# AltoidsCanary.net
KiCad netlist of a schematic drawn in EasyEDA
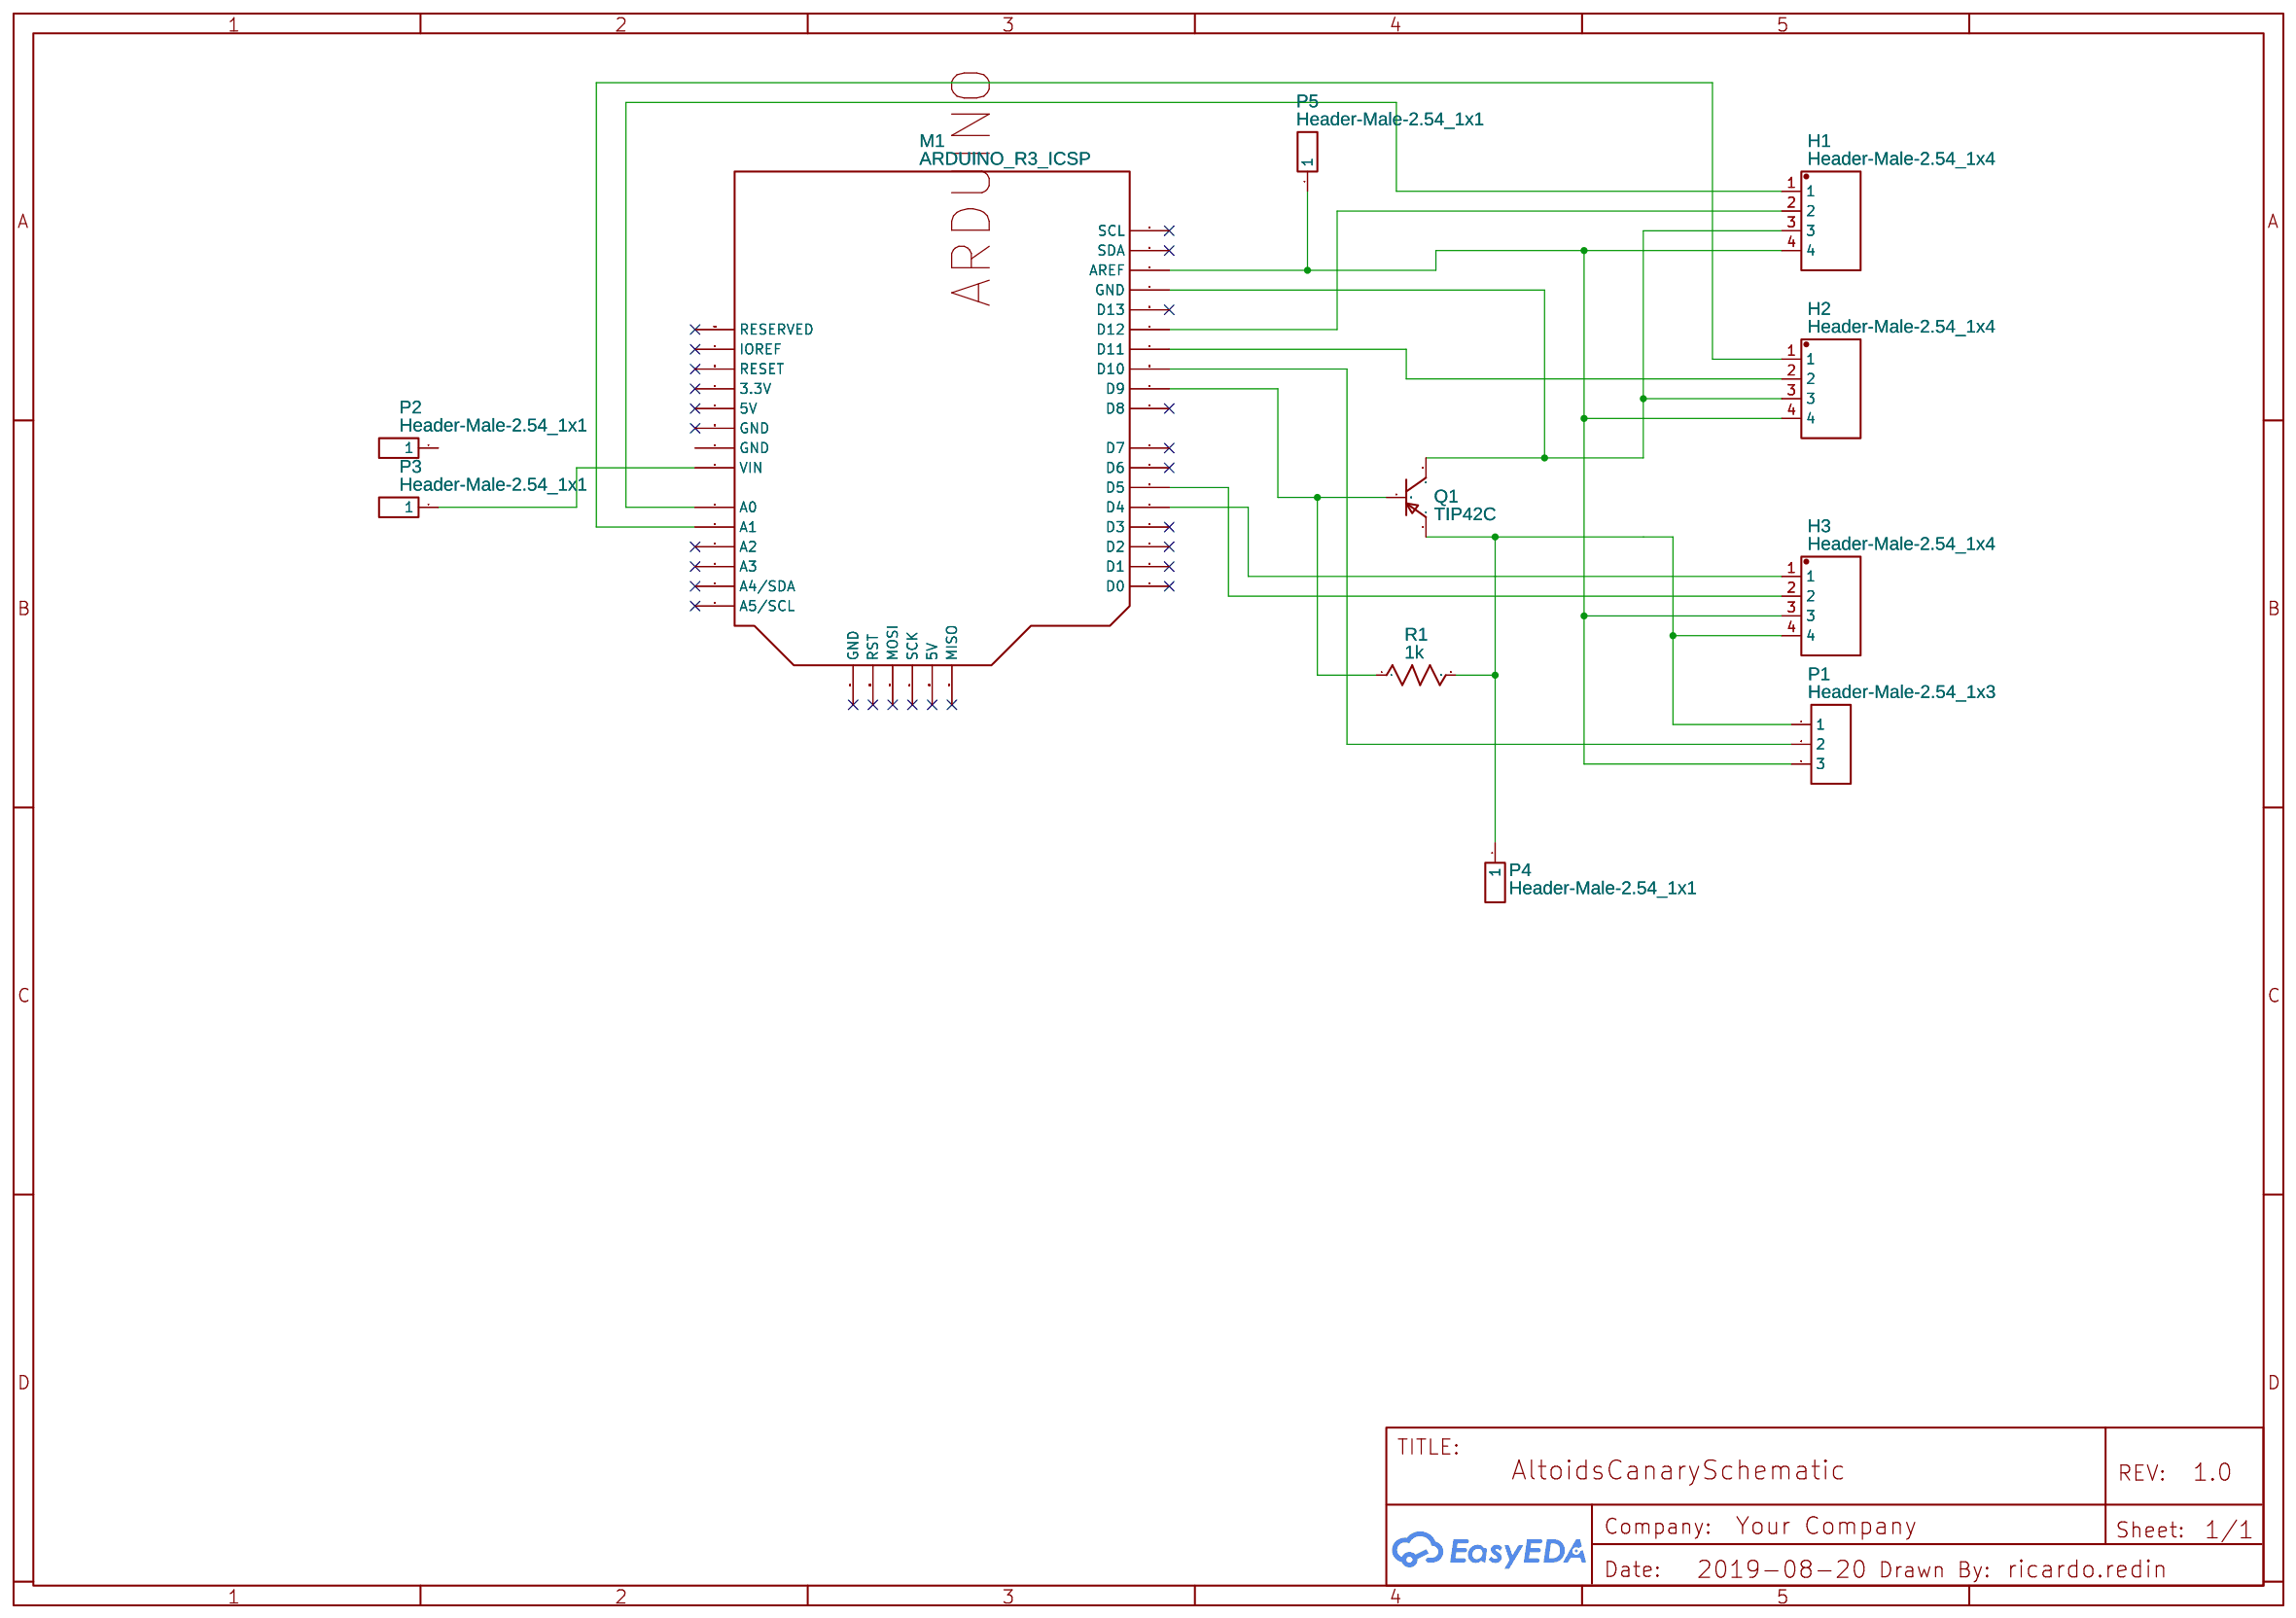
[diagram p0: schematic sheet]

(export (version "E")
  (design (tool "Eeschema 10.0.6"))
  (components
    (comp (ref "H1")
      (value "Header-Male-2.54_1x4")
      (fields
        (field (name "BOM_Manufacturer Part") "210S-1*4P L=11.6MMGold-plated black")
        (field (name "BOM_Supplier Part") "C124378")
      )
      (libsource (lib "") (part "Unknown_915_105"))
    )
    (comp (ref "H2")
      (value "Header-Male-2.54_1x4")
      (fields
        (field (name "BOM_Manufacturer Part") "210S-1*4P L=11.6MMGold-plated black")
        (field (name "BOM_Supplier Part") "C124378")
      )
      (libsource (lib "") (part "Unknown_915_190"))
    )
    (comp (ref "H3")
      (value "Header-Male-2.54_1x4")
      (fields
        (field (name "BOM_Manufacturer Part") "210S-1*4P L=11.6MMGold-plated black")
        (field (name "BOM_Supplier Part") "C124378")
      )
      (libsource (lib "") (part "Unknown_915_300"))
    )
    (comp (ref "M1")
      (value "ARDUINO_R3_ICSP")
      (fields (field (name "BOM_Manufacturer Part") "?"))
      (libsource (lib "") (part "Unknown_365_80"))
    )
    (comp (ref "P1")
      (value "Header-Male-2.54_1x3")
      (fields
        (field (name "BOM_Manufacturer Part") "Header2.54mm 1*3P")
        (field (name "BOM_Supplier Part") "C49257")
      )
      (libsource (lib "") (part "Unknown_915_370"))
    )
    (comp (ref "P2")
      (value "Header-Male-2.54_1x1")
      (fields (field (name "BOM_Supplier Part") "C81276"))
      (libsource (lib "") (part "Unknown_200_220"))
    )
    (comp (ref "P3")
      (value "Header-Male-2.54_1x1")
      (fields (field (name "BOM_Supplier Part") "C81276"))
      (libsource (lib "") (part "Unknown_200_250"))
    )
    (comp (ref "P4")
      (value "Header-Male-2.54_1x1")
      (fields (field (name "BOM_Supplier Part") "C81276"))
      (libsource (lib "") (part "Unknown_750_435"))
    )
    (comp (ref "P5")
      (value "Header-Male-2.54_1x1")
      (fields (field (name "BOM_Supplier Part") "C81276"))
      (libsource (lib "") (part "Unknown_655_75"))
    )
    (comp (ref "Q1")
      (value "TIP42C")
      (fields (field (name "BOM_Supplier Part") "C92311"))
      (libsource (lib "") (part "Unknown_705_245"))
    )
    (comp (ref "R1") (value "1k") (libsource (lib "") (part "Res_AXIAL-0.3(1/8W)_US")))
  )
  (nets
    (net (code "1") (name "Net-(H1-Pad1)") (class "Default")
      (node (ref "H1") (pin "1") (pinfunction "1_1") (pintype "unspecified"))
      (node (ref "M1") (pin "A0") (pinfunction "A0_A0") (pintype "unspecified"))
    )
    (net (code "2") (name "Net-(H1-Pad2)") (class "Default")
      (node (ref "H1") (pin "2") (pinfunction "2_2") (pintype "unspecified"))
      (node (ref "M1") (pin "D12") (pinfunction "D12_D12") (pintype "unspecified"))
    )
    (net (code "3") (name "Net-(H1-Pad4)") (class "Default")
      (node (ref "H1") (pin "4") (pinfunction "4_4") (pintype "unspecified"))
      (node (ref "H2") (pin "4") (pinfunction "4_4") (pintype "unspecified"))
      (node (ref "H3") (pin "3") (pinfunction "3_3") (pintype "unspecified"))
      (node (ref "M1") (pin "AREF") (pinfunction "AREF_AREF") (pintype "unspecified"))
      (node (ref "P1") (pin "3") (pinfunction "3_3") (pintype "input"))
      (node (ref "P5") (pin "1") (pinfunction "1_1") (pintype "input"))
    )
    (net (code "4") (name "Net-(H2-Pad1)") (class "Default")
      (node (ref "H2") (pin "1") (pinfunction "1_1") (pintype "unspecified"))
      (node (ref "M1") (pin "A1") (pinfunction "A1_A1") (pintype "unspecified"))
    )
    (net (code "5") (name "Net-(H2-Pad2)") (class "Default")
      (node (ref "H2") (pin "2") (pinfunction "2_2") (pintype "unspecified"))
      (node (ref "M1") (pin "D11") (pinfunction "D11_D11") (pintype "unspecified"))
    )
    (net (code "6") (name "Net-(H3-Pad1)") (class "Default")
      (node (ref "H3") (pin "1") (pinfunction "1_1") (pintype "unspecified"))
      (node (ref "M1") (pin "D4") (pinfunction "D4_D4") (pintype "unspecified"))
    )
    (net (code "7") (name "Net-(H3-Pad2)") (class "Default")
      (node (ref "H3") (pin "2") (pinfunction "2_2") (pintype "unspecified"))
      (node (ref "M1") (pin "D5") (pinfunction "D5_D5") (pintype "unspecified"))
    )
    (net (code "8") (name "Net-(M1-PadD10)") (class "Default")
      (node (ref "M1") (pin "D10") (pinfunction "D10_D10") (pintype "unspecified"))
      (node (ref "P1") (pin "2") (pinfunction "2_2") (pintype "input"))
    )
    (net (code "9") (name "Net-(M1-PadVIN)") (class "Default")
      (node (ref "M1") (pin "VIN") (pinfunction "VIN_VIN") (pintype "passive"))
      (node (ref "P3") (pin "1") (pinfunction "1_1") (pintype "input"))
    )
    (net (code "10") (name "Net-(Q1-B)") (class "Default")
      (node (ref "M1") (pin "D9") (pinfunction "D9_D9") (pintype "unspecified"))
      (node (ref "Q1") (pin "1") (pinfunction "B_1") (pintype "unspecified"))
      (node (ref "R1") (pin "1") (pinfunction "1_1") (pintype "unspecified"))
    )
    (net (code "11") (name "Net-(Q1-C)") (class "Default")
      (node (ref "H1") (pin "3") (pinfunction "3_3") (pintype "unspecified"))
      (node (ref "H2") (pin "3") (pinfunction "3_3") (pintype "unspecified"))
      (node (ref "M1") (pin "GND") (pinfunction "GND_GND") (pintype "passive"))
      (node (ref "Q1") (pin "2") (pinfunction "C_2") (pintype "unspecified"))
    )
    (net (code "12") (name "Net-(Q1-E)") (class "Default")
      (node (ref "H3") (pin "4") (pinfunction "4_4") (pintype "unspecified"))
      (node (ref "P1") (pin "1") (pinfunction "1_1") (pintype "input"))
      (node (ref "P4") (pin "1") (pinfunction "1_1") (pintype "input"))
      (node (ref "Q1") (pin "3") (pinfunction "E_3") (pintype "unspecified"))
      (node (ref "R1") (pin "2") (pinfunction "2_2") (pintype "unspecified"))
    )
    (net (code "13") (name "unconnected-(M1-5V-Pad5V_ICSP)") (class "Default")
      (node (ref "M1") (pin "5V_ICSP") (pinfunction "5V_5V_ICSP") (pintype "unspecified+no_connect"))
    )
    (net (code "14") (name "unconnected-(M1-A4{slash}SDA-PadA4)") (class "Default")
      (node (ref "M1") (pin "A4") (pinfunction "A4/SDA_A4") (pintype "unspecified+no_connect"))
    )
    (net (code "15") (name "unconnected-(M1-A5{slash}SCL-PadA5)") (class "Default")
      (node (ref "M1") (pin "A5") (pinfunction "A5/SCL_A5") (pintype "unspecified+no_connect"))
    )
    (net (code "16") (name "unconnected-(M1-Pad3.3V)") (class "Default")
      (node (ref "M1") (pin "3.3V") (pinfunction "3.3V_3.3V") (pintype "passive+no_connect"))
    )
    (net (code "17") (name "unconnected-(M1-Pad5V)") (class "Default")
      (node (ref "M1") (pin "5V") (pinfunction "5V_5V") (pintype "passive+no_connect"))
    )
    (net (code "18") (name "unconnected-(M1-PadA2)") (class "Default")
      (node (ref "M1") (pin "A2") (pinfunction "A2_A2") (pintype "unspecified+no_connect"))
    )
    (net (code "19") (name "unconnected-(M1-PadA3)") (class "Default")
      (node (ref "M1") (pin "A3") (pinfunction "A3_A3") (pintype "unspecified+no_connect"))
    )
    (net (code "20") (name "unconnected-(M1-PadD0)") (class "Default")
      (node (ref "M1") (pin "D0") (pinfunction "D0_D0") (pintype "unspecified+no_connect"))
    )
    (net (code "21") (name "unconnected-(M1-PadD1)") (class "Default")
      (node (ref "M1") (pin "D1") (pinfunction "D1_D1") (pintype "unspecified+no_connect"))
    )
    (net (code "22") (name "unconnected-(M1-PadD2)") (class "Default")
      (node (ref "M1") (pin "D2") (pinfunction "D2_D2") (pintype "unspecified+no_connect"))
    )
    (net (code "23") (name "unconnected-(M1-PadD3)") (class "Default")
      (node (ref "M1") (pin "D3") (pinfunction "D3_D3") (pintype "unspecified+no_connect"))
    )
    (net (code "24") (name "unconnected-(M1-PadD6)") (class "Default")
      (node (ref "M1") (pin "D6") (pinfunction "D6_D6") (pintype "unspecified+no_connect"))
    )
    (net (code "25") (name "unconnected-(M1-PadD7)") (class "Default")
      (node (ref "M1") (pin "D7") (pinfunction "D7_D7") (pintype "unspecified+no_connect"))
    )
    (net (code "26") (name "unconnected-(M1-PadD8)") (class "Default")
      (node (ref "M1") (pin "D8") (pinfunction "D8_D8") (pintype "unspecified+no_connect"))
    )
    (net (code "27") (name "unconnected-(M1-PadD13)") (class "Default")
      (node (ref "M1") (pin "D13") (pinfunction "D13_D13") (pintype "unspecified+no_connect"))
    )
    (net (code "28") (name "unconnected-(M1-PadGND)") (class "Default")
      (node (ref "M1") (pin "GND") (pinfunction "GND_GND") (pintype "unspecified+no_connect"))
    )
    (net (code "29") (name "unconnected-(M1-PadGND)") (class "Default")
      (node (ref "M1") (pin "GND") (pinfunction "GND_GND") (pintype "passive"))
    )
    (net (code "30") (name "unconnected-(M1-PadGND)_1") (class "Default")
      (node (ref "M1") (pin "GND") (pinfunction "GND_GND") (pintype "passive+no_connect"))
    )
    (net (code "31") (name "unconnected-(M1-PadIOREF)") (class "Default")
      (node (ref "M1") (pin "IOREF") (pinfunction "IOREF_IOREF") (pintype "output+no_connect"))
    )
    (net (code "32") (name "unconnected-(M1-PadMISO)") (class "Default")
      (node (ref "M1") (pin "MISO") (pinfunction "MISO_MISO") (pintype "unspecified+no_connect"))
    )
    (net (code "33") (name "unconnected-(M1-PadMOSI)") (class "Default")
      (node (ref "M1") (pin "MOSI") (pinfunction "MOSI_MOSI") (pintype "unspecified+no_connect"))
    )
    (net (code "34") (name "unconnected-(M1-PadRESERVED)") (class "Default")
      (node (ref "M1") (pin "RESERVED") (pinfunction "RESERVED_RESERVED") (pintype "unspecified+no_connect"))
    )
    (net (code "35") (name "unconnected-(M1-PadRESET)") (class "Default")
      (node (ref "M1") (pin "RESET") (pinfunction "RESET_RESET") (pintype "unspecified+no_connect"))
    )
    (net (code "36") (name "unconnected-(M1-PadSCK)") (class "Default")
      (node (ref "M1") (pin "SCK") (pinfunction "SCK_SCK") (pintype "unspecified+no_connect"))
    )
    (net (code "37") (name "unconnected-(M1-PadSCL)") (class "Default")
      (node (ref "M1") (pin "SCL") (pinfunction "SCL_SCL") (pintype "unspecified+no_connect"))
    )
    (net (code "38") (name "unconnected-(M1-PadSDA)") (class "Default")
      (node (ref "M1") (pin "SDA") (pinfunction "SDA_SDA") (pintype "unspecified+no_connect"))
    )
    (net (code "39") (name "unconnected-(M1-RST-PadRESET_ICSP)") (class "Default")
      (node (ref "M1") (pin "RESET_ICSP") (pinfunction "RST_RESET_ICSP") (pintype "unspecified+no_connect"))
    )
    (net (code "40") (name "unconnected-(P2-Pad1)") (class "Default")
      (node (ref "P2") (pin "1") (pinfunction "1_1") (pintype "input"))
    )
  )
)
